# 003-00005.net
KiCad netlist of a schematic drawn in Altium Designer
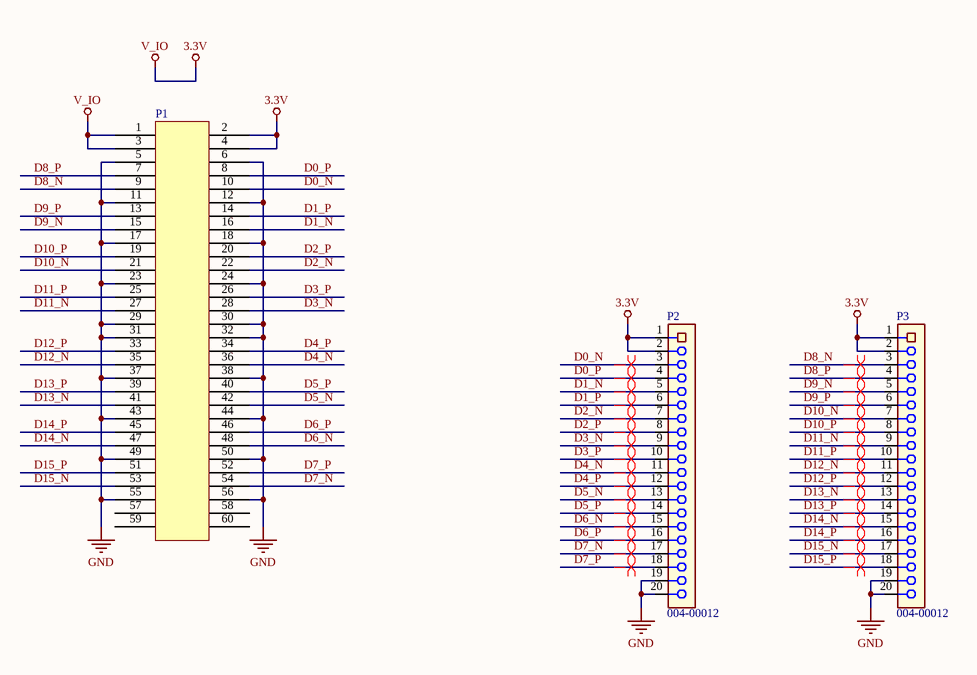
[diagram p0: 003-00005.SchDoc]

(export (version "E")
  (design (tool "Eeschema 10.0.6"))
  (components
    (comp (ref "P1")
      (value "~")
      (footprint "005-00024")
      (description "Connector, PCB edge, MEC8, 30x2 Pin")
      (fields (field (name "PART NUMBER") "008-00005"))
      (libsource (lib "CES Component Library") (part "004-00022"))
    )
    (comp (ref "P2")
      (value "004-00012")
      (footprint "005-00014")
      (description "CONN RCPT 2x10")
      (fields
        (field (name "PART NUMBER") "017-00011")
        (field (name "MANUFACTURER1 PART NUMBER") "54102-S05-10LF")
      )
      (libsource (lib "CES Component Library") (part "004-00012"))
    )
    (comp (ref "P3")
      (value "004-00012")
      (footprint "005-00014")
      (description "CONN RCPT 2x10")
      (fields
        (field (name "PART NUMBER") "017-00011")
        (field (name "MANUFACTURER1 PART NUMBER") "54102-S05-10LF")
      )
      (libsource (lib "CES Component Library") (part "004-00012"))
    )
  )
  (nets
    (net (code "1") (name "/D0_N") (class "Default")
      (node (ref "P1") (pin "10") (pinfunction "10_10") (pintype "passive"))
      (node (ref "P2") (pin "3") (pinfunction "3_3") (pintype "passive"))
    )
    (net (code "2") (name "/D0_P") (class "Default")
      (node (ref "P1") (pin "8") (pinfunction "8_8") (pintype "passive"))
      (node (ref "P2") (pin "4") (pinfunction "4_4") (pintype "passive"))
    )
    (net (code "3") (name "/D1_N") (class "Default")
      (node (ref "P1") (pin "16") (pinfunction "16_16") (pintype "passive"))
      (node (ref "P2") (pin "5") (pinfunction "5_5") (pintype "passive"))
    )
    (net (code "4") (name "/D1_P") (class "Default")
      (node (ref "P1") (pin "14") (pinfunction "14_14") (pintype "passive"))
      (node (ref "P2") (pin "6") (pinfunction "6_6") (pintype "passive"))
    )
    (net (code "5") (name "/D2_N") (class "Default")
      (node (ref "P1") (pin "22") (pinfunction "22_22") (pintype "passive"))
      (node (ref "P2") (pin "7") (pinfunction "7_7") (pintype "passive"))
    )
    (net (code "6") (name "/D2_P") (class "Default")
      (node (ref "P1") (pin "20") (pinfunction "20_20") (pintype "passive"))
      (node (ref "P2") (pin "8") (pinfunction "8_8") (pintype "passive"))
    )
    (net (code "7") (name "/D3_N") (class "Default")
      (node (ref "P1") (pin "28") (pinfunction "28_28") (pintype "passive"))
      (node (ref "P2") (pin "9") (pinfunction "9_9") (pintype "passive"))
    )
    (net (code "8") (name "/D3_P") (class "Default")
      (node (ref "P1") (pin "26") (pinfunction "26_26") (pintype "passive"))
      (node (ref "P2") (pin "10") (pinfunction "10_10") (pintype "passive"))
    )
    (net (code "9") (name "/D4_N") (class "Default")
      (node (ref "P1") (pin "36") (pinfunction "36_36") (pintype "passive"))
      (node (ref "P2") (pin "11") (pinfunction "11_11") (pintype "passive"))
    )
    (net (code "10") (name "/D4_P") (class "Default")
      (node (ref "P1") (pin "34") (pinfunction "34_34") (pintype "passive"))
      (node (ref "P2") (pin "12") (pinfunction "12_12") (pintype "passive"))
    )
    (net (code "11") (name "/D5_N") (class "Default")
      (node (ref "P1") (pin "42") (pinfunction "42_42") (pintype "passive"))
      (node (ref "P2") (pin "13") (pinfunction "13_13") (pintype "passive"))
    )
    (net (code "12") (name "/D5_P") (class "Default")
      (node (ref "P1") (pin "40") (pinfunction "40_40") (pintype "passive"))
      (node (ref "P2") (pin "14") (pinfunction "14_14") (pintype "passive"))
    )
    (net (code "13") (name "/D6_N") (class "Default")
      (node (ref "P1") (pin "48") (pinfunction "48_48") (pintype "passive"))
      (node (ref "P2") (pin "15") (pinfunction "15_15") (pintype "passive"))
    )
    (net (code "14") (name "/D6_P") (class "Default")
      (node (ref "P1") (pin "46") (pinfunction "46_46") (pintype "passive"))
      (node (ref "P2") (pin "16") (pinfunction "16_16") (pintype "passive"))
    )
    (net (code "15") (name "/D7_N") (class "Default")
      (node (ref "P1") (pin "54") (pinfunction "54_54") (pintype "passive"))
      (node (ref "P2") (pin "17") (pinfunction "17_17") (pintype "passive"))
    )
    (net (code "16") (name "/D7_P") (class "Default")
      (node (ref "P1") (pin "52") (pinfunction "52_52") (pintype "passive"))
      (node (ref "P2") (pin "18") (pinfunction "18_18") (pintype "passive"))
    )
    (net (code "17") (name "/D8_N") (class "Default")
      (node (ref "P1") (pin "9") (pinfunction "9_9") (pintype "passive"))
      (node (ref "P3") (pin "3") (pinfunction "3_3") (pintype "passive"))
    )
    (net (code "18") (name "/D8_P") (class "Default")
      (node (ref "P1") (pin "7") (pinfunction "7_7") (pintype "passive"))
      (node (ref "P3") (pin "4") (pinfunction "4_4") (pintype "passive"))
    )
    (net (code "19") (name "/D9_N") (class "Default")
      (node (ref "P1") (pin "15") (pinfunction "15_15") (pintype "passive"))
      (node (ref "P3") (pin "5") (pinfunction "5_5") (pintype "passive"))
    )
    (net (code "20") (name "/D9_P") (class "Default")
      (node (ref "P1") (pin "13") (pinfunction "13_13") (pintype "passive"))
      (node (ref "P3") (pin "6") (pinfunction "6_6") (pintype "passive"))
    )
    (net (code "21") (name "/D10_N") (class "Default")
      (node (ref "P1") (pin "21") (pinfunction "21_21") (pintype "passive"))
      (node (ref "P3") (pin "7") (pinfunction "7_7") (pintype "passive"))
    )
    (net (code "22") (name "/D10_P") (class "Default")
      (node (ref "P1") (pin "19") (pinfunction "19_19") (pintype "passive"))
      (node (ref "P3") (pin "8") (pinfunction "8_8") (pintype "passive"))
    )
    (net (code "23") (name "/D11_N") (class "Default")
      (node (ref "P1") (pin "27") (pinfunction "27_27") (pintype "passive"))
      (node (ref "P3") (pin "9") (pinfunction "9_9") (pintype "passive"))
    )
    (net (code "24") (name "/D11_P") (class "Default")
      (node (ref "P1") (pin "25") (pinfunction "25_25") (pintype "passive"))
      (node (ref "P3") (pin "10") (pinfunction "10_10") (pintype "passive"))
    )
    (net (code "25") (name "/D12_N") (class "Default")
      (node (ref "P1") (pin "35") (pinfunction "35_35") (pintype "passive"))
      (node (ref "P3") (pin "11") (pinfunction "11_11") (pintype "passive"))
    )
    (net (code "26") (name "/D12_P") (class "Default")
      (node (ref "P1") (pin "33") (pinfunction "33_33") (pintype "passive"))
      (node (ref "P3") (pin "12") (pinfunction "12_12") (pintype "passive"))
    )
    (net (code "27") (name "/D13_N") (class "Default")
      (node (ref "P1") (pin "41") (pinfunction "41_41") (pintype "passive"))
      (node (ref "P3") (pin "13") (pinfunction "13_13") (pintype "passive"))
    )
    (net (code "28") (name "/D13_P") (class "Default")
      (node (ref "P1") (pin "39") (pinfunction "39_39") (pintype "passive"))
      (node (ref "P3") (pin "14") (pinfunction "14_14") (pintype "passive"))
    )
    (net (code "29") (name "/D14_N") (class "Default")
      (node (ref "P1") (pin "47") (pinfunction "47_47") (pintype "passive"))
      (node (ref "P3") (pin "15") (pinfunction "15_15") (pintype "passive"))
    )
    (net (code "30") (name "/D14_P") (class "Default")
      (node (ref "P1") (pin "45") (pinfunction "45_45") (pintype "passive"))
      (node (ref "P3") (pin "16") (pinfunction "16_16") (pintype "passive"))
    )
    (net (code "31") (name "/D15_N") (class "Default")
      (node (ref "P1") (pin "53") (pinfunction "53_53") (pintype "passive"))
      (node (ref "P3") (pin "17") (pinfunction "17_17") (pintype "passive"))
    )
    (net (code "32") (name "/D15_P") (class "Default")
      (node (ref "P1") (pin "51") (pinfunction "51_51") (pintype "passive"))
      (node (ref "P3") (pin "18") (pinfunction "18_18") (pintype "passive"))
    )
    (net (code "33") (name "3.3V") (class "Default")
      (node (ref "P1") (pin "1") (pinfunction "1_1") (pintype "passive"))
      (node (ref "P1") (pin "2") (pinfunction "2_2") (pintype "passive"))
      (node (ref "P1") (pin "3") (pinfunction "3_3") (pintype "passive"))
      (node (ref "P1") (pin "4") (pinfunction "4_4") (pintype "passive"))
      (node (ref "P2") (pin "1") (pinfunction "1_1") (pintype "passive"))
      (node (ref "P2") (pin "2") (pinfunction "2_2") (pintype "passive"))
      (node (ref "P3") (pin "1") (pinfunction "1_1") (pintype "passive"))
      (node (ref "P3") (pin "2") (pinfunction "2_2") (pintype "passive"))
    )
    (net (code "34") (name "GND") (class "Default")
      (node (ref "P1") (pin "11") (pinfunction "11_11") (pintype "passive"))
      (node (ref "P1") (pin "12") (pinfunction "12_12") (pintype "passive"))
      (node (ref "P1") (pin "17") (pinfunction "17_17") (pintype "passive"))
      (node (ref "P1") (pin "18") (pinfunction "18_18") (pintype "passive"))
      (node (ref "P1") (pin "23") (pinfunction "23_23") (pintype "passive"))
      (node (ref "P1") (pin "24") (pinfunction "24_24") (pintype "passive"))
      (node (ref "P1") (pin "29") (pinfunction "29_29") (pintype "passive"))
      (node (ref "P1") (pin "30") (pinfunction "30_30") (pintype "passive"))
      (node (ref "P1") (pin "31") (pinfunction "31_31") (pintype "passive"))
      (node (ref "P1") (pin "32") (pinfunction "32_32") (pintype "passive"))
      (node (ref "P1") (pin "37") (pinfunction "37_37") (pintype "passive"))
      (node (ref "P1") (pin "38") (pinfunction "38_38") (pintype "passive"))
      (node (ref "P1") (pin "43") (pinfunction "43_43") (pintype "passive"))
      (node (ref "P1") (pin "44") (pinfunction "44_44") (pintype "passive"))
      (node (ref "P1") (pin "49") (pinfunction "49_49") (pintype "passive"))
      (node (ref "P1") (pin "5") (pinfunction "5_5") (pintype "passive"))
      (node (ref "P1") (pin "50") (pinfunction "50_50") (pintype "passive"))
      (node (ref "P1") (pin "55") (pinfunction "55_55") (pintype "passive"))
      (node (ref "P1") (pin "56") (pinfunction "56_56") (pintype "passive"))
      (node (ref "P1") (pin "6") (pinfunction "6_6") (pintype "passive"))
      (node (ref "P2") (pin "19") (pinfunction "19_19") (pintype "passive"))
      (node (ref "P2") (pin "20") (pinfunction "20_20") (pintype "passive"))
      (node (ref "P3") (pin "19") (pinfunction "19_19") (pintype "passive"))
      (node (ref "P3") (pin "20") (pinfunction "20_20") (pintype "passive"))
    )
    (net (code "35") (name "unconnected-(P1-Pad57)") (class "Default")
      (node (ref "P1") (pin "57") (pinfunction "57_57") (pintype "passive"))
    )
    (net (code "36") (name "unconnected-(P1-Pad58)") (class "Default")
      (node (ref "P1") (pin "58") (pinfunction "58_58") (pintype "passive"))
    )
    (net (code "37") (name "unconnected-(P1-Pad59)") (class "Default")
      (node (ref "P1") (pin "59") (pinfunction "59_59") (pintype "passive"))
    )
    (net (code "38") (name "unconnected-(P1-Pad60)") (class "Default")
      (node (ref "P1") (pin "60") (pinfunction "60_60") (pintype "passive"))
    )
  )
)
